# Right_Channel_Audio.net
KiCad netlist of a schematic drawn in Altium Designer
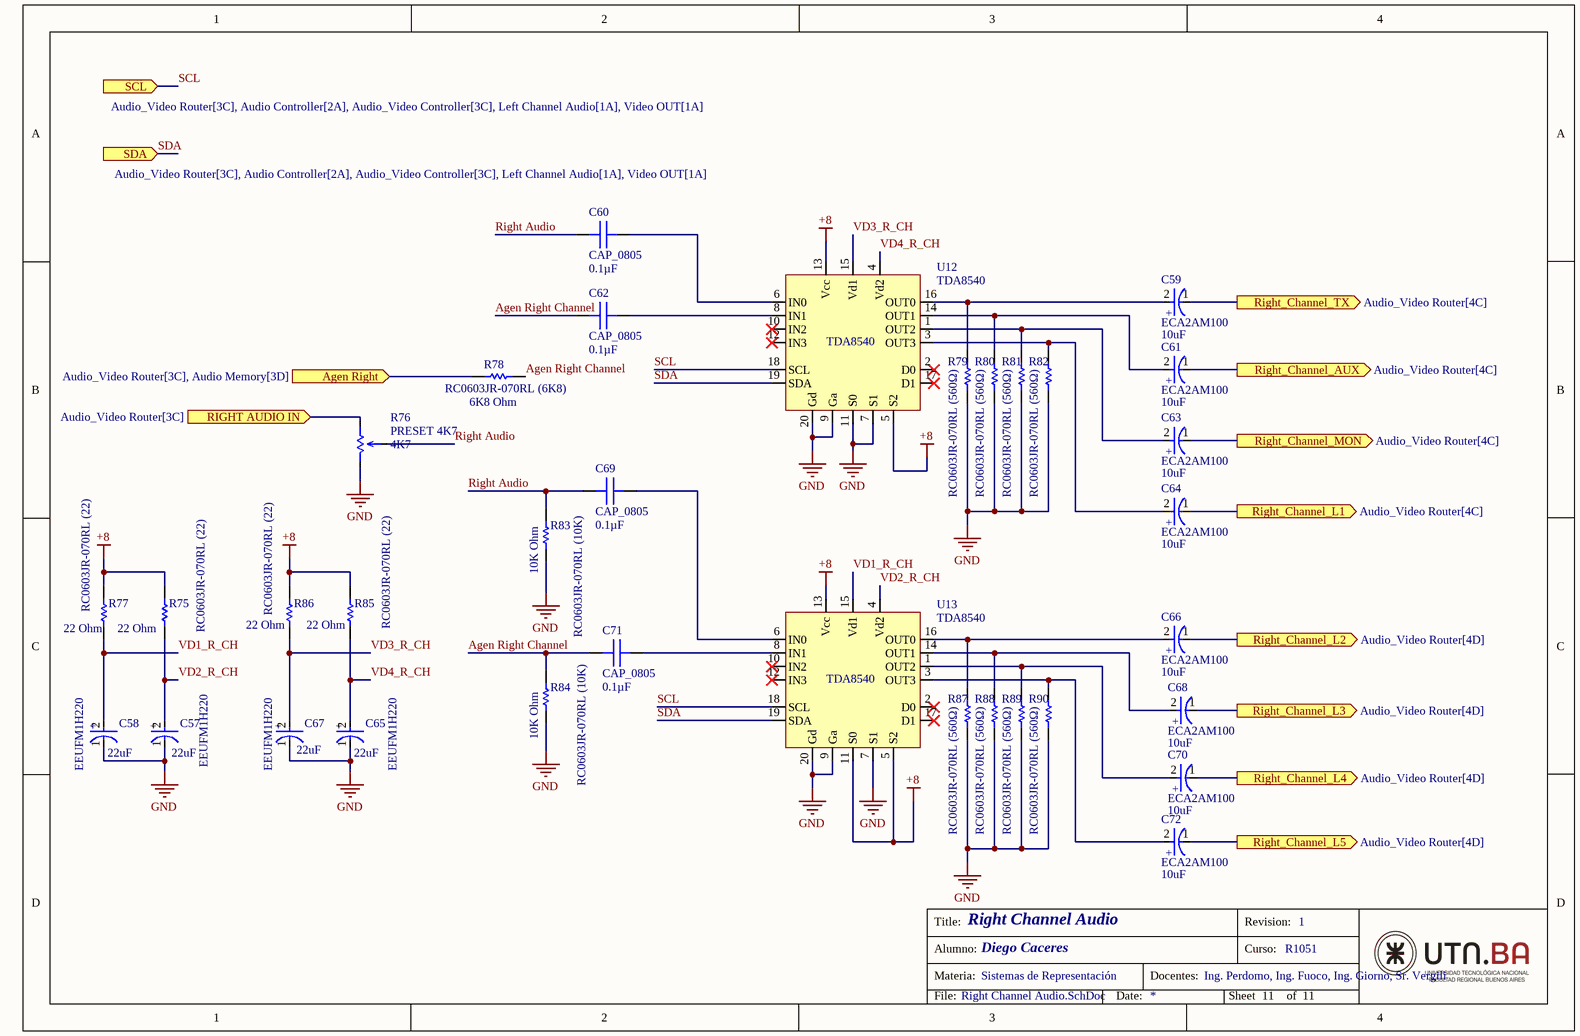
[diagram p0: Right Channel Audio.SchDoc]

(export (version "E")
  (design (tool "Eeschema 10.0.6"))
  (components
    (comp (ref "C57")
      (value "EEUFM1H220")
      (footprint "FP-RAD-TH-D_5_0_5-L_11_1-MFG")
      (description "Aluminum Electrolytic Capacitors (Radial Lead Type) 22uF ±20% 50V")
      (fields
        (field (name "TOLERANCE") "20%")
        (field (name "VOLTAGE") "50V")
        (field (name "CAPACITANCE") "22uF")
      )
      (libsource (lib "Altium Content Vault") (part "a00bbbee19879c290e62620ae7e47b1"))
    )
    (comp (ref "C58")
      (value "EEUFM1H220")
      (footprint "FP-RAD-TH-D_5_0_5-L_11_1-MFG")
      (description "Aluminum Electrolytic Capacitors (Radial Lead Type) 22uF ±20% 50V")
      (fields
        (field (name "TOLERANCE") "20%")
        (field (name "VOLTAGE") "50V")
        (field (name "CAPACITANCE") "22uF")
      )
      (libsource (lib "Altium Content Vault") (part "a00bbbee19879c290e62620ae7e47b1"))
    )
    (comp (ref "C59")
      (value "ECA2AM100")
      (footprint "FP-RAD-TH-D_5_0_5-L_11_1-MFG")
      (description "Aluminum Electrolytic Capacitors (Radial Lead Type) 10uF ±20% 100V")
      (fields
        (field (name "CAPACITANCE") "10uF")
        (field (name "VOLTAGE") "100V")
        (field (name "TOLERANCE") "20%")
      )
      (libsource (lib "Altium Content Vault") (part "a00bbbee19879c290e62620ae7e47b1"))
    )
    (comp (ref "C60")
      (value "CAP_0805")
      (footprint "0805_CAPACITOR_DCACERES")
      (description "Capacitor SMD, encapsulado 0805")
      (fields (field (name "ALTIUM_VALUE") "0.1µF"))
      (libsource (lib "PF_Schlib") (part "CAPACITOR_0805_Caceres"))
    )
    (comp (ref "C61")
      (value "ECA2AM100")
      (footprint "FP-RAD-TH-D_5_0_5-L_11_1-MFG")
      (description "Aluminum Electrolytic Capacitors (Radial Lead Type) 10uF ±20% 100V")
      (fields
        (field (name "CAPACITANCE") "10uF")
        (field (name "VOLTAGE") "100V")
        (field (name "TOLERANCE") "20%")
      )
      (libsource (lib "Altium Content Vault") (part "a00bbbee19879c290e62620ae7e47b1"))
    )
    (comp (ref "C62")
      (value "CAP_0805")
      (footprint "0805_CAPACITOR_DCACERES")
      (description "Capacitor SMD, encapsulado 0805")
      (fields (field (name "ALTIUM_VALUE") "0.1µF"))
      (libsource (lib "PF_Schlib") (part "CAPACITOR_0805_Caceres"))
    )
    (comp (ref "C63")
      (value "ECA2AM100")
      (footprint "FP-RAD-TH-D_5_0_5-L_11_1-MFG")
      (description "Aluminum Electrolytic Capacitors (Radial Lead Type) 10uF ±20% 100V")
      (fields
        (field (name "CAPACITANCE") "10uF")
        (field (name "VOLTAGE") "100V")
        (field (name "TOLERANCE") "20%")
      )
      (libsource (lib "Altium Content Vault") (part "a00bbbee19879c290e62620ae7e47b1"))
    )
    (comp (ref "C64")
      (value "ECA2AM100")
      (footprint "FP-RAD-TH-D_5_0_5-L_11_1-MFG")
      (description "Aluminum Electrolytic Capacitors (Radial Lead Type) 10uF ±20% 100V")
      (fields
        (field (name "CAPACITANCE") "10uF")
        (field (name "VOLTAGE") "100V")
        (field (name "TOLERANCE") "20%")
      )
      (libsource (lib "Altium Content Vault") (part "a00bbbee19879c290e62620ae7e47b1"))
    )
    (comp (ref "C65")
      (value "EEUFM1H220")
      (footprint "FP-RAD-TH-D_5_0_5-L_11_1-MFG")
      (description "Aluminum Electrolytic Capacitors (Radial Lead Type) 22uF ±20% 50V")
      (fields
        (field (name "TOLERANCE") "20%")
        (field (name "VOLTAGE") "50V")
        (field (name "CAPACITANCE") "22uF")
      )
      (libsource (lib "Altium Content Vault") (part "a00bbbee19879c290e62620ae7e47b1"))
    )
    (comp (ref "C66")
      (value "ECA2AM100")
      (footprint "FP-RAD-TH-D_5_0_5-L_11_1-MFG")
      (description "Aluminum Electrolytic Capacitors (Radial Lead Type) 10uF ±20% 100V")
      (fields
        (field (name "CAPACITANCE") "10uF")
        (field (name "VOLTAGE") "100V")
        (field (name "TOLERANCE") "20%")
      )
      (libsource (lib "Altium Content Vault") (part "a00bbbee19879c290e62620ae7e47b1"))
    )
    (comp (ref "C67")
      (value "EEUFM1H220")
      (footprint "FP-RAD-TH-D_5_0_5-L_11_1-MFG")
      (description "Aluminum Electrolytic Capacitors (Radial Lead Type) 22uF ±20% 50V")
      (fields
        (field (name "TOLERANCE") "20%")
        (field (name "VOLTAGE") "50V")
        (field (name "CAPACITANCE") "22uF")
      )
      (libsource (lib "Altium Content Vault") (part "a00bbbee19879c290e62620ae7e47b1"))
    )
    (comp (ref "C68")
      (value "ECA2AM100")
      (footprint "FP-RAD-TH-D_5_0_5-L_11_1-MFG")
      (description "Aluminum Electrolytic Capacitors (Radial Lead Type) 10uF ±20% 100V")
      (fields
        (field (name "CAPACITANCE") "10uF")
        (field (name "VOLTAGE") "100V")
        (field (name "TOLERANCE") "20%")
      )
      (libsource (lib "Altium Content Vault") (part "a00bbbee19879c290e62620ae7e47b1"))
    )
    (comp (ref "C69")
      (value "CAP_0805")
      (footprint "0805_CAPACITOR_DCACERES")
      (description "Capacitor SMD, encapsulado 0805")
      (fields (field (name "ALTIUM_VALUE") "0.1µF"))
      (libsource (lib "PF_Schlib") (part "CAPACITOR_0805_Caceres"))
    )
    (comp (ref "C70")
      (value "ECA2AM100")
      (footprint "FP-RAD-TH-D_5_0_5-L_11_1-MFG")
      (description "Aluminum Electrolytic Capacitors (Radial Lead Type) 10uF ±20% 100V")
      (fields
        (field (name "CAPACITANCE") "10uF")
        (field (name "VOLTAGE") "100V")
        (field (name "TOLERANCE") "20%")
      )
      (libsource (lib "Altium Content Vault") (part "a00bbbee19879c290e62620ae7e47b1"))
    )
    (comp (ref "C71")
      (value "CAP_0805")
      (footprint "0805_CAPACITOR_DCACERES")
      (description "Capacitor SMD, encapsulado 0805")
      (fields (field (name "ALTIUM_VALUE") "0.1µF"))
      (libsource (lib "PF_Schlib") (part "CAPACITOR_0805_Caceres"))
    )
    (comp (ref "C72")
      (value "ECA2AM100")
      (footprint "FP-RAD-TH-D_5_0_5-L_11_1-MFG")
      (description "Aluminum Electrolytic Capacitors (Radial Lead Type) 10uF ±20% 100V")
      (fields
        (field (name "CAPACITANCE") "10uF")
        (field (name "VOLTAGE") "100V")
        (field (name "TOLERANCE") "20%")
      )
      (libsource (lib "Altium Content Vault") (part "a00bbbee19879c290e62620ae7e47b1"))
    )
    (comp (ref "R75")
      (value "RC0603JR-070RL (22)")
      (footprint "RESC1608X55X25ML10T15")
      (description "Chip Resistor, 0 Ohm, +/- 5%, 0.1 W, -55 to 155 degC, 0603 (1608 Metric), RoHS, Tape and Reel")
      (fields
        (field (name "TOLERANCE") "5%")
        (field (name "RESISTANCE") "22 Ohm")
        (field (name "MANUFACTURER") "Yageo")
      )
      (libsource (lib "Altium Content Vault") (part "RES-2"))
    )
    (comp (ref "R76")
      (value "PRESET 4K7")
      (footprint "3386P_PRESET_4K7_DCaceres")
      (description "Preset 4K7, Thru HoleManufacturer Part Search 3386P-1-472LF")
      (fields (field (name "ALTIUM_VALUE") "4K7") (field (name "PARTNUMBER") "3386P-1-472LF"))
      (libsource (lib "PF_Schlib") (part "Preset_4K7_Caceres"))
    )
    (comp (ref "R77")
      (value "RC0603JR-070RL (22)")
      (footprint "RESC1608X55X25ML10T15")
      (description "Chip Resistor, 0 Ohm, +/- 5%, 0.1 W, -55 to 155 degC, 0603 (1608 Metric), RoHS, Tape and Reel")
      (fields
        (field (name "TOLERANCE") "5%")
        (field (name "RESISTANCE") "22 Ohm")
        (field (name "MANUFACTURER") "Yageo")
      )
      (libsource (lib "Altium Content Vault") (part "RES-2"))
    )
    (comp (ref "R78")
      (value "RC0603JR-070RL (6K8)")
      (footprint "RESC1608X55X25ML10T15")
      (description "Chip Resistor, 0 Ohm, +/- 5%, 0.1 W, -55 to 155 degC, 0603 (1608 Metric), RoHS, Tape and Reel")
      (fields
        (field (name "TOLERANCE") "5%")
        (field (name "RESISTANCE") "6K8 Ohm")
        (field (name "MANUFACTURER") "Yageo")
      )
      (libsource (lib "Altium Content Vault") (part "RES-2"))
    )
    (comp (ref "R79")
      (value "RC0603JR-070RL (560Ω)")
      (footprint "RESC1608X55X25ML10T15")
      (description "Chip Resistor, 0 Ohm, +/- 5%, 0.1 W, -55 to 155 degC, 0603 (1608 Metric), RoHS, Tape and Reel")
      (fields (field (name "TOLERANCE") "5%") (field (name "MANUFACTURER") "Yageo"))
      (libsource (lib "Altium Content Vault") (part "RES-2"))
    )
    (comp (ref "R80")
      (value "RC0603JR-070RL (560Ω)")
      (footprint "RESC1608X55X25ML10T15")
      (description "Chip Resistor, 0 Ohm, +/- 5%, 0.1 W, -55 to 155 degC, 0603 (1608 Metric), RoHS, Tape and Reel")
      (fields (field (name "TOLERANCE") "5%") (field (name "MANUFACTURER") "Yageo"))
      (libsource (lib "Altium Content Vault") (part "RES-2"))
    )
    (comp (ref "R81")
      (value "RC0603JR-070RL (560Ω)")
      (footprint "RESC1608X55X25ML10T15")
      (description "Chip Resistor, 0 Ohm, +/- 5%, 0.1 W, -55 to 155 degC, 0603 (1608 Metric), RoHS, Tape and Reel")
      (fields (field (name "TOLERANCE") "5%") (field (name "MANUFACTURER") "Yageo"))
      (libsource (lib "Altium Content Vault") (part "RES-2"))
    )
    (comp (ref "R82")
      (value "RC0603JR-070RL (560Ω)")
      (footprint "RESC1608X55X25ML10T15")
      (description "Chip Resistor, 0 Ohm, +/- 5%, 0.1 W, -55 to 155 degC, 0603 (1608 Metric), RoHS, Tape and Reel")
      (fields (field (name "TOLERANCE") "5%") (field (name "MANUFACTURER") "Yageo"))
      (libsource (lib "Altium Content Vault") (part "RES-2"))
    )
    (comp (ref "R83")
      (value "RC0603JR-070RL (10K)")
      (footprint "RESC1608X55X25ML10T15")
      (description "Chip Resistor, 0 Ohm, +/- 5%, 0.1 W, -55 to 155 degC, 0603 (1608 Metric), RoHS, Tape and Reel")
      (fields
        (field (name "TOLERANCE") "5%")
        (field (name "RESISTANCE") "10K Ohm")
        (field (name "MANUFACTURER") "Yageo")
      )
      (libsource (lib "Altium Content Vault") (part "RES-2"))
    )
    (comp (ref "R84")
      (value "RC0603JR-070RL (10K)")
      (footprint "RESC1608X55X25ML10T15")
      (description "Chip Resistor, 0 Ohm, +/- 5%, 0.1 W, -55 to 155 degC, 0603 (1608 Metric), RoHS, Tape and Reel")
      (fields
        (field (name "TOLERANCE") "5%")
        (field (name "RESISTANCE") "10K Ohm")
        (field (name "MANUFACTURER") "Yageo")
      )
      (libsource (lib "Altium Content Vault") (part "RES-2"))
    )
    (comp (ref "R85")
      (value "RC0603JR-070RL (22)")
      (footprint "RESC1608X55X25ML10T15")
      (description "Chip Resistor, 0 Ohm, +/- 5%, 0.1 W, -55 to 155 degC, 0603 (1608 Metric), RoHS, Tape and Reel")
      (fields
        (field (name "TOLERANCE") "5%")
        (field (name "RESISTANCE") "22 Ohm")
        (field (name "MANUFACTURER") "Yageo")
      )
      (libsource (lib "Altium Content Vault") (part "RES-2"))
    )
    (comp (ref "R86")
      (value "RC0603JR-070RL (22)")
      (footprint "RESC1608X55X25ML10T15")
      (description "Chip Resistor, 0 Ohm, +/- 5%, 0.1 W, -55 to 155 degC, 0603 (1608 Metric), RoHS, Tape and Reel")
      (fields
        (field (name "TOLERANCE") "5%")
        (field (name "RESISTANCE") "22 Ohm")
        (field (name "MANUFACTURER") "Yageo")
      )
      (libsource (lib "Altium Content Vault") (part "RES-2"))
    )
    (comp (ref "R87")
      (value "RC0603JR-070RL (560Ω)")
      (footprint "RESC1608X55X25ML10T15")
      (description "Chip Resistor, 0 Ohm, +/- 5%, 0.1 W, -55 to 155 degC, 0603 (1608 Metric), RoHS, Tape and Reel")
      (fields (field (name "TOLERANCE") "5%") (field (name "MANUFACTURER") "Yageo"))
      (libsource (lib "Altium Content Vault") (part "RES-2"))
    )
    (comp (ref "R88")
      (value "RC0603JR-070RL (560Ω)")
      (footprint "RESC1608X55X25ML10T15")
      (description "Chip Resistor, 0 Ohm, +/- 5%, 0.1 W, -55 to 155 degC, 0603 (1608 Metric), RoHS, Tape and Reel")
      (fields (field (name "TOLERANCE") "5%") (field (name "MANUFACTURER") "Yageo"))
      (libsource (lib "Altium Content Vault") (part "RES-2"))
    )
    (comp (ref "R89")
      (value "RC0603JR-070RL (560Ω)")
      (footprint "RESC1608X55X25ML10T15")
      (description "Chip Resistor, 0 Ohm, +/- 5%, 0.1 W, -55 to 155 degC, 0603 (1608 Metric), RoHS, Tape and Reel")
      (fields (field (name "TOLERANCE") "5%") (field (name "MANUFACTURER") "Yageo"))
      (libsource (lib "Altium Content Vault") (part "RES-2"))
    )
    (comp (ref "R90")
      (value "RC0603JR-070RL (560Ω)")
      (footprint "RESC1608X55X25ML10T15")
      (description "Chip Resistor, 0 Ohm, +/- 5%, 0.1 W, -55 to 155 degC, 0603 (1608 Metric), RoHS, Tape and Reel")
      (fields (field (name "TOLERANCE") "5%") (field (name "MANUFACTURER") "Yageo"))
      (libsource (lib "Altium Content Vault") (part "RES-2"))
    )
    (comp (ref "U12")
      (value "TDA8540")
      (footprint "SOT146-1_DIP20_TDA8540_DCACERES")
      (description "TDA8540, Thtu Hole\r\nPlastic dual in-line package; 20 leads (300 mil); DIP20; SOT146-1.")
      (libsource (lib "PF_Schlib") (part "TDA8540_Caceres"))
    )
    (comp (ref "U13")
      (value "TDA8540")
      (footprint "SOT146-1_DIP20_TDA8540_DCACERES")
      (description "TDA8540, Thtu Hole\r\nPlastic dual in-line package; 20 leads (300 mil); DIP20; SOT146-1.")
      (libsource (lib "PF_Schlib") (part "TDA8540_Caceres"))
    )
  )
  (nets
    (net (code "1") (name "+8") (class "Default")
      (node (ref "R75") (pin "2") (pinfunction "2_2") (pintype "passive"))
      (node (ref "R77") (pin "2") (pinfunction "2_2") (pintype "passive"))
      (node (ref "R85") (pin "2") (pinfunction "2_2") (pintype "passive"))
      (node (ref "R86") (pin "2") (pinfunction "2_2") (pintype "passive"))
      (node (ref "U12") (pin "13") (pinfunction "Vcc_13") (pintype "passive"))
      (node (ref "U12") (pin "5") (pinfunction "S2_5") (pintype "passive"))
      (node (ref "U13") (pin "11") (pinfunction "S0_11") (pintype "passive"))
      (node (ref "U13") (pin "13") (pinfunction "Vcc_13") (pintype "passive"))
      (node (ref "U13") (pin "5") (pinfunction "S2_5") (pintype "passive"))
    )
    (net (code "2") (name "/Agen Right") (class "Default")
      (node (ref "R78") (pin "1") (pinfunction "1_1") (pintype "passive"))
    )
    (net (code "3") (name "/Agen Right Channel") (class "Default")
      (node (ref "C62") (pin "1") (pinfunction "1_1") (pintype "passive"))
      (node (ref "C71") (pin "1") (pinfunction "1_1") (pintype "passive"))
      (node (ref "R78") (pin "2") (pinfunction "2_2") (pintype "passive"))
      (node (ref "R84") (pin "2") (pinfunction "2_2") (pintype "passive"))
    )
    (net (code "4") (name "/RIGHT AUDIO IN") (class "Default")
      (node (ref "R76") (pin "2") (pinfunction "1_2") (pintype "passive"))
    )
    (net (code "5") (name "/Right Audio") (class "Default")
      (node (ref "C60") (pin "1") (pinfunction "1_1") (pintype "passive"))
      (node (ref "C69") (pin "1") (pinfunction "1_1") (pintype "passive"))
      (node (ref "R76") (pin "3") (pinfunction "3_3") (pintype "passive"))
      (node (ref "R83") (pin "2") (pinfunction "2_2") (pintype "passive"))
    )
    (net (code "6") (name "/Right_Channel_AUX") (class "Default")
      (node (ref "C61") (pin "1") (pinfunction "C_1") (pintype "passive"))
    )
    (net (code "7") (name "/Right_Channel_L1") (class "Default")
      (node (ref "C64") (pin "1") (pinfunction "C_1") (pintype "passive"))
    )
    (net (code "8") (name "/Right_Channel_L2") (class "Default")
      (node (ref "C66") (pin "1") (pinfunction "C_1") (pintype "passive"))
    )
    (net (code "9") (name "/Right_Channel_L3") (class "Default")
      (node (ref "C68") (pin "1") (pinfunction "C_1") (pintype "passive"))
    )
    (net (code "10") (name "/Right_Channel_L4") (class "Default")
      (node (ref "C70") (pin "1") (pinfunction "C_1") (pintype "passive"))
    )
    (net (code "11") (name "/Right_Channel_L5") (class "Default")
      (node (ref "C72") (pin "1") (pinfunction "C_1") (pintype "passive"))
    )
    (net (code "12") (name "/Right_Channel_MON") (class "Default")
      (node (ref "C63") (pin "1") (pinfunction "C_1") (pintype "passive"))
    )
    (net (code "13") (name "/Right_Channel_TX") (class "Default")
      (node (ref "C59") (pin "1") (pinfunction "C_1") (pintype "passive"))
    )
    (net (code "14") (name "/SCL") (class "Default")
      (node (ref "U12") (pin "18") (pinfunction "SCL_18") (pintype "passive"))
      (node (ref "U13") (pin "18") (pinfunction "SCL_18") (pintype "passive"))
    )
    (net (code "15") (name "/SDA") (class "Default")
      (node (ref "U12") (pin "19") (pinfunction "SDA_19") (pintype "passive"))
      (node (ref "U13") (pin "19") (pinfunction "SDA_19") (pintype "passive"))
    )
    (net (code "16") (name "/VD1_R_CH") (class "Default")
      (node (ref "C58") (pin "2") (pinfunction "A_2") (pintype "passive"))
      (node (ref "R77") (pin "1") (pinfunction "1_1") (pintype "passive"))
      (node (ref "U13") (pin "15") (pinfunction "Vd1_15") (pintype "passive"))
    )
    (net (code "17") (name "/VD2_R_CH") (class "Default")
      (node (ref "C57") (pin "2") (pinfunction "A_2") (pintype "passive"))
      (node (ref "R75") (pin "1") (pinfunction "1_1") (pintype "passive"))
      (node (ref "U13") (pin "4") (pinfunction "Vd2_4") (pintype "passive"))
    )
    (net (code "18") (name "/VD3_R_CH") (class "Default")
      (node (ref "C67") (pin "2") (pinfunction "A_2") (pintype "passive"))
      (node (ref "R86") (pin "1") (pinfunction "1_1") (pintype "passive"))
      (node (ref "U12") (pin "15") (pinfunction "Vd1_15") (pintype "passive"))
    )
    (net (code "19") (name "/VD4_R_CH") (class "Default")
      (node (ref "C65") (pin "2") (pinfunction "A_2") (pintype "passive"))
      (node (ref "R85") (pin "1") (pinfunction "1_1") (pintype "passive"))
      (node (ref "U12") (pin "4") (pinfunction "Vd2_4") (pintype "passive"))
    )
    (net (code "20") (name "GND") (class "Default")
      (node (ref "C57") (pin "1") (pinfunction "C_1") (pintype "passive"))
      (node (ref "C58") (pin "1") (pinfunction "C_1") (pintype "passive"))
      (node (ref "C65") (pin "1") (pinfunction "C_1") (pintype "passive"))
      (node (ref "C67") (pin "1") (pinfunction "C_1") (pintype "passive"))
      (node (ref "R76") (pin "1") (pinfunction "1_1") (pintype "passive"))
      (node (ref "R79") (pin "2") (pinfunction "2_2") (pintype "passive"))
      (node (ref "R80") (pin "2") (pinfunction "2_2") (pintype "passive"))
      (node (ref "R81") (pin "2") (pinfunction "2_2") (pintype "passive"))
      (node (ref "R82") (pin "2") (pinfunction "2_2") (pintype "passive"))
      (node (ref "R83") (pin "1") (pinfunction "1_1") (pintype "passive"))
      (node (ref "R84") (pin "1") (pinfunction "1_1") (pintype "passive"))
      (node (ref "R87") (pin "2") (pinfunction "2_2") (pintype "passive"))
      (node (ref "R88") (pin "2") (pinfunction "2_2") (pintype "passive"))
      (node (ref "R89") (pin "2") (pinfunction "2_2") (pintype "passive"))
      (node (ref "R90") (pin "2") (pinfunction "2_2") (pintype "passive"))
      (node (ref "U12") (pin "11") (pinfunction "S0_11") (pintype "passive"))
      (node (ref "U12") (pin "20") (pinfunction "Gd_20") (pintype "passive"))
      (node (ref "U12") (pin "7") (pinfunction "S1_7") (pintype "passive"))
      (node (ref "U12") (pin "9") (pinfunction "Ga_9") (pintype "passive"))
      (node (ref "U13") (pin "20") (pinfunction "Gd_20") (pintype "passive"))
      (node (ref "U13") (pin "7") (pinfunction "S1_7") (pintype "passive"))
      (node (ref "U13") (pin "9") (pinfunction "Ga_9") (pintype "passive"))
    )
    (net (code "21") (name "Net-(C59-A)") (class "Default")
      (node (ref "C59") (pin "2") (pinfunction "A_2") (pintype "passive"))
      (node (ref "R79") (pin "1") (pinfunction "1_1") (pintype "passive"))
      (node (ref "U12") (pin "16") (pinfunction "OUT0_16") (pintype "passive"))
    )
    (net (code "22") (name "Net-(C61-A)") (class "Default")
      (node (ref "C61") (pin "2") (pinfunction "A_2") (pintype "passive"))
      (node (ref "R80") (pin "1") (pinfunction "1_1") (pintype "passive"))
      (node (ref "U12") (pin "14") (pinfunction "OUT1_14") (pintype "passive"))
    )
    (net (code "23") (name "Net-(C63-A)") (class "Default")
      (node (ref "C63") (pin "2") (pinfunction "A_2") (pintype "passive"))
      (node (ref "R81") (pin "1") (pinfunction "1_1") (pintype "passive"))
      (node (ref "U12") (pin "1") (pinfunction "OUT2_1") (pintype "passive"))
    )
    (net (code "24") (name "Net-(C64-A)") (class "Default")
      (node (ref "C64") (pin "2") (pinfunction "A_2") (pintype "passive"))
      (node (ref "R82") (pin "1") (pinfunction "1_1") (pintype "passive"))
      (node (ref "U12") (pin "3") (pinfunction "OUT3_3") (pintype "passive"))
    )
    (net (code "25") (name "Net-(C66-A)") (class "Default")
      (node (ref "C66") (pin "2") (pinfunction "A_2") (pintype "passive"))
      (node (ref "R87") (pin "1") (pinfunction "1_1") (pintype "passive"))
      (node (ref "U13") (pin "16") (pinfunction "OUT0_16") (pintype "passive"))
    )
    (net (code "26") (name "Net-(C68-A)") (class "Default")
      (node (ref "C68") (pin "2") (pinfunction "A_2") (pintype "passive"))
      (node (ref "R88") (pin "1") (pinfunction "1_1") (pintype "passive"))
      (node (ref "U13") (pin "14") (pinfunction "OUT1_14") (pintype "passive"))
    )
    (net (code "27") (name "Net-(C70-A)") (class "Default")
      (node (ref "C70") (pin "2") (pinfunction "A_2") (pintype "passive"))
      (node (ref "R89") (pin "1") (pinfunction "1_1") (pintype "passive"))
      (node (ref "U13") (pin "1") (pinfunction "OUT2_1") (pintype "passive"))
    )
    (net (code "28") (name "Net-(C72-A)") (class "Default")
      (node (ref "C72") (pin "2") (pinfunction "A_2") (pintype "passive"))
      (node (ref "R90") (pin "1") (pinfunction "1_1") (pintype "passive"))
      (node (ref "U13") (pin "3") (pinfunction "OUT3_3") (pintype "passive"))
    )
    (net (code "29") (name "Net-(U12-IN0)") (class "Default")
      (node (ref "C60") (pin "2") (pinfunction "2_2") (pintype "passive"))
      (node (ref "U12") (pin "6") (pinfunction "IN0_6") (pintype "passive"))
    )
    (net (code "30") (name "Net-(U12-IN1)") (class "Default")
      (node (ref "C62") (pin "2") (pinfunction "2_2") (pintype "passive"))
      (node (ref "U12") (pin "8") (pinfunction "IN1_8") (pintype "passive"))
    )
    (net (code "31") (name "Net-(U13-IN0)") (class "Default")
      (node (ref "C69") (pin "2") (pinfunction "2_2") (pintype "passive"))
      (node (ref "U13") (pin "6") (pinfunction "IN0_6") (pintype "passive"))
    )
    (net (code "32") (name "Net-(U13-IN1)") (class "Default")
      (node (ref "C71") (pin "2") (pinfunction "2_2") (pintype "passive"))
      (node (ref "U13") (pin "8") (pinfunction "IN1_8") (pintype "passive"))
    )
    (net (code "33") (name "unconnected-(U12-D0-Pad2)") (class "Default")
      (node (ref "U12") (pin "2") (pinfunction "D0_2") (pintype "passive+no_connect"))
    )
    (net (code "34") (name "unconnected-(U12-D1-Pad17)") (class "Default")
      (node (ref "U12") (pin "17") (pinfunction "D1_17") (pintype "passive+no_connect"))
    )
    (net (code "35") (name "unconnected-(U12-IN2-Pad10)") (class "Default")
      (node (ref "U12") (pin "10") (pinfunction "IN2_10") (pintype "passive+no_connect"))
    )
    (net (code "36") (name "unconnected-(U12-IN3-Pad12)") (class "Default")
      (node (ref "U12") (pin "12") (pinfunction "IN3_12") (pintype "passive+no_connect"))
    )
    (net (code "37") (name "unconnected-(U13-D0-Pad2)") (class "Default")
      (node (ref "U13") (pin "2") (pinfunction "D0_2") (pintype "passive+no_connect"))
    )
    (net (code "38") (name "unconnected-(U13-D1-Pad17)") (class "Default")
      (node (ref "U13") (pin "17") (pinfunction "D1_17") (pintype "passive+no_connect"))
    )
    (net (code "39") (name "unconnected-(U13-IN2-Pad10)") (class "Default")
      (node (ref "U13") (pin "10") (pinfunction "IN2_10") (pintype "passive+no_connect"))
    )
    (net (code "40") (name "unconnected-(U13-IN3-Pad12)") (class "Default")
      (node (ref "U13") (pin "12") (pinfunction "IN3_12") (pintype "passive+no_connect"))
    )
  )
)
